# HDMI2.net
KiCad netlist of a schematic drawn in Altium Designer
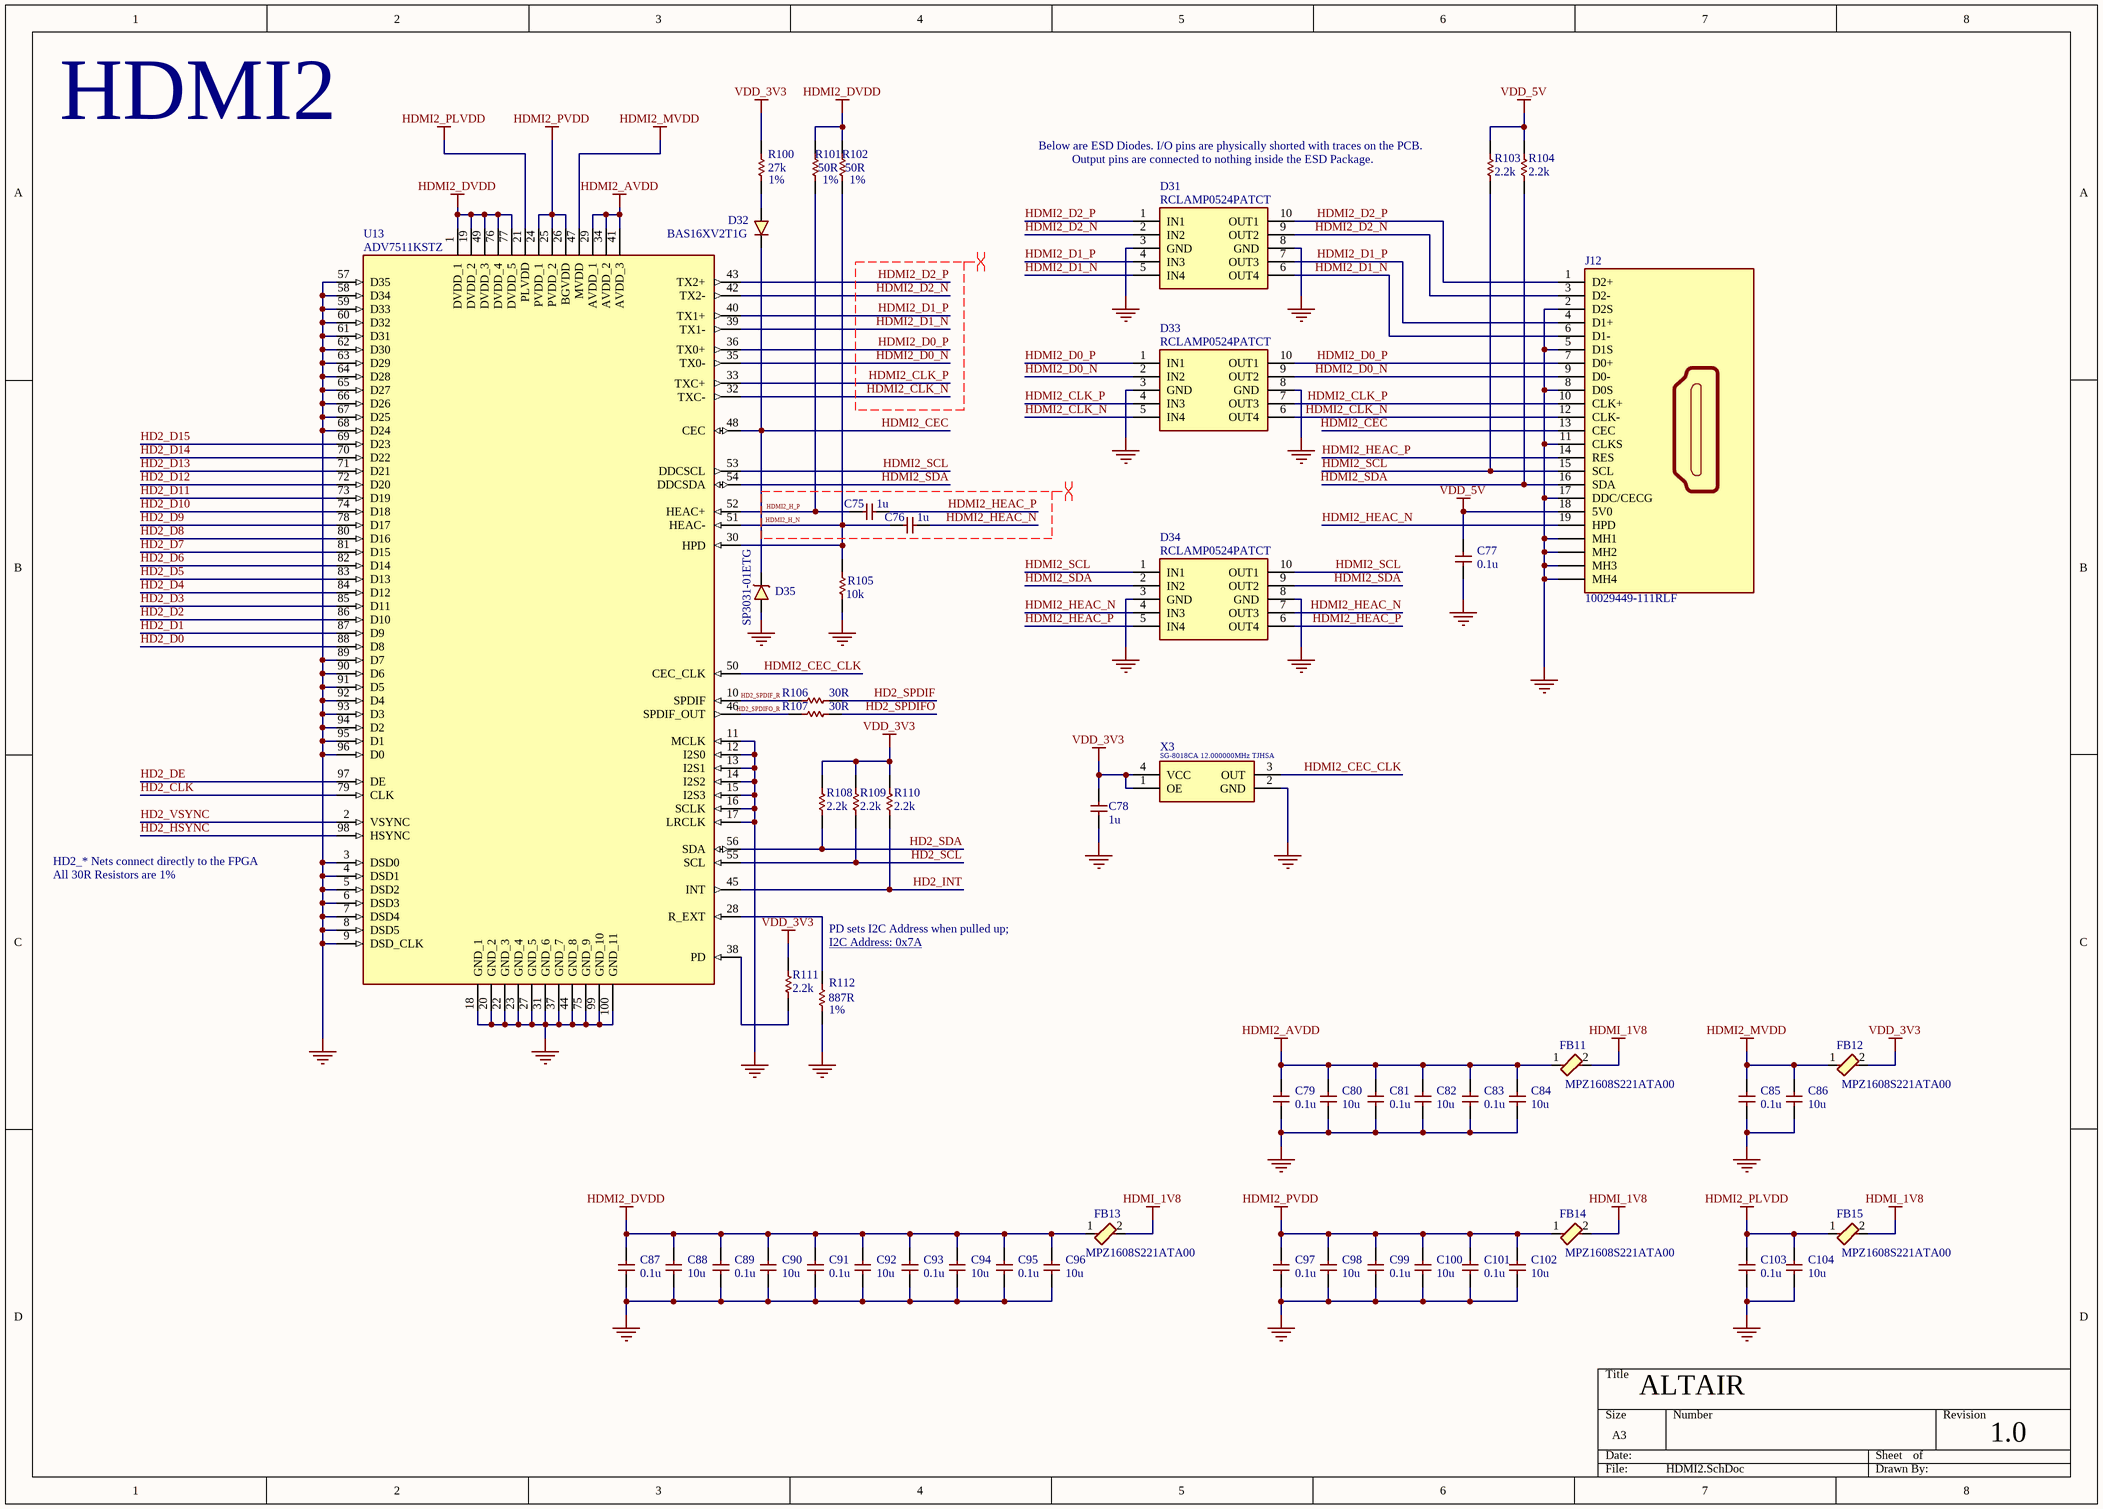
[diagram p0: HDMI2.SchDoc]

(export (version "E")
  (design (tool "Eeschema 10.0.6"))
  (components
    (comp (ref "C75")
      (value "1u")
      (footprint "CAP_0402")
      (description "Capacitor SMD 0402")
      (fields (field (name "JLCPCB PART #") "C14445") (field (name "PART NO") "CL05A105KP5NNNC"))
      (libsource (lib "personalGenericLib") (part "CAP_0402"))
    )
    (comp (ref "C76")
      (value "1u")
      (footprint "CAP_0402")
      (description "Capacitor SMD 0402")
      (fields (field (name "JLCPCB PART #") "C14445") (field (name "PART NO") "CL05A105KP5NNNC"))
      (libsource (lib "personalGenericLib") (part "CAP_0402"))
    )
    (comp (ref "C77")
      (value "0.1u")
      (footprint "CAP_0402")
      (description "Capacitor SMD 0402")
      (fields (field (name "PART NO") "CL05B104KO5NNNC") (field (name "JLCPCB PART #") "C338112"))
      (libsource (lib "personalGenericLib") (part "CAP_0402"))
    )
    (comp (ref "C78")
      (value "1u")
      (footprint "CAP_0402")
      (description "Capacitor SMD 0402")
      (fields (field (name "JLCPCB PART #") "C14445") (field (name "PART NO") "CL05A105KP5NNNC"))
      (libsource (lib "personalGenericLib") (part "CAP_0402"))
    )
    (comp (ref "C79")
      (value "0.1u")
      (footprint "CAP_0402")
      (description "Capacitor SMD 0402")
      (fields (field (name "PART NO") "CL05B104KO5NNNC") (field (name "JLCPCB PART #") "C338112"))
      (libsource (lib "personalGenericLib") (part "CAP_0402"))
    )
    (comp (ref "C80")
      (value "10u")
      (footprint "CAP_0402")
      (description "Capacitor SMD 0402")
      (fields (field (name "JLCPCB PART #") "C315248") (field (name "PART NO") "CL05A106MP5NUNC"))
      (libsource (lib "personalGenericLib") (part "CAP_0402"))
    )
    (comp (ref "C81")
      (value "0.1u")
      (footprint "CAP_0402")
      (description "Capacitor SMD 0402")
      (fields (field (name "PART NO") "CL05B104KO5NNNC") (field (name "JLCPCB PART #") "C338112"))
      (libsource (lib "personalGenericLib") (part "CAP_0402"))
    )
    (comp (ref "C82")
      (value "10u")
      (footprint "CAP_0402")
      (description "Capacitor SMD 0402")
      (fields (field (name "JLCPCB PART #") "C315248") (field (name "PART NO") "CL05A106MP5NUNC"))
      (libsource (lib "personalGenericLib") (part "CAP_0402"))
    )
    (comp (ref "C83")
      (value "0.1u")
      (footprint "CAP_0402")
      (description "Capacitor SMD 0402")
      (fields (field (name "PART NO") "CL05B104KO5NNNC") (field (name "JLCPCB PART #") "C338112"))
      (libsource (lib "personalGenericLib") (part "CAP_0402"))
    )
    (comp (ref "C84")
      (value "10u")
      (footprint "CAP_0402")
      (description "Capacitor SMD 0402")
      (fields (field (name "JLCPCB PART #") "C315248") (field (name "PART NO") "CL05A106MP5NUNC"))
      (libsource (lib "personalGenericLib") (part "CAP_0402"))
    )
    (comp (ref "C85")
      (value "0.1u")
      (footprint "CAP_0402")
      (description "Capacitor SMD 0402")
      (fields (field (name "PART NO") "CL05B104KO5NNNC") (field (name "JLCPCB PART #") "C338112"))
      (libsource (lib "personalGenericLib") (part "CAP_0402"))
    )
    (comp (ref "C86")
      (value "10u")
      (footprint "CAP_0402")
      (description "Capacitor SMD 0402")
      (fields (field (name "JLCPCB PART #") "C315248") (field (name "PART NO") "CL05A106MP5NUNC"))
      (libsource (lib "personalGenericLib") (part "CAP_0402"))
    )
    (comp (ref "C87")
      (value "0.1u")
      (footprint "CAP_0402")
      (description "Capacitor SMD 0402")
      (fields (field (name "PART NO") "CL05B104KO5NNNC") (field (name "JLCPCB PART #") "C338112"))
      (libsource (lib "personalGenericLib") (part "CAP_0402"))
    )
    (comp (ref "C88")
      (value "10u")
      (footprint "CAP_0402")
      (description "Capacitor SMD 0402")
      (fields (field (name "JLCPCB PART #") "C315248") (field (name "PART NO") "CL05A106MP5NUNC"))
      (libsource (lib "personalGenericLib") (part "CAP_0402"))
    )
    (comp (ref "C89")
      (value "0.1u")
      (footprint "CAP_0402")
      (description "Capacitor SMD 0402")
      (fields (field (name "PART NO") "CL05B104KO5NNNC") (field (name "JLCPCB PART #") "C338112"))
      (libsource (lib "personalGenericLib") (part "CAP_0402"))
    )
    (comp (ref "C90")
      (value "10u")
      (footprint "CAP_0402")
      (description "Capacitor SMD 0402")
      (fields (field (name "JLCPCB PART #") "C315248") (field (name "PART NO") "CL05A106MP5NUNC"))
      (libsource (lib "personalGenericLib") (part "CAP_0402"))
    )
    (comp (ref "C91")
      (value "0.1u")
      (footprint "CAP_0402")
      (description "Capacitor SMD 0402")
      (fields (field (name "PART NO") "CL05B104KO5NNNC") (field (name "JLCPCB PART #") "C338112"))
      (libsource (lib "personalGenericLib") (part "CAP_0402"))
    )
    (comp (ref "C92")
      (value "10u")
      (footprint "CAP_0402")
      (description "Capacitor SMD 0402")
      (fields (field (name "JLCPCB PART #") "C315248") (field (name "PART NO") "CL05A106MP5NUNC"))
      (libsource (lib "personalGenericLib") (part "CAP_0402"))
    )
    (comp (ref "C93")
      (value "0.1u")
      (footprint "CAP_0402")
      (description "Capacitor SMD 0402")
      (fields (field (name "PART NO") "CL05B104KO5NNNC") (field (name "JLCPCB PART #") "C338112"))
      (libsource (lib "personalGenericLib") (part "CAP_0402"))
    )
    (comp (ref "C94")
      (value "10u")
      (footprint "CAP_0402")
      (description "Capacitor SMD 0402")
      (fields (field (name "JLCPCB PART #") "C315248") (field (name "PART NO") "CL05A106MP5NUNC"))
      (libsource (lib "personalGenericLib") (part "CAP_0402"))
    )
    (comp (ref "C95")
      (value "0.1u")
      (footprint "CAP_0402")
      (description "Capacitor SMD 0402")
      (fields (field (name "PART NO") "CL05B104KO5NNNC") (field (name "JLCPCB PART #") "C338112"))
      (libsource (lib "personalGenericLib") (part "CAP_0402"))
    )
    (comp (ref "C96")
      (value "10u")
      (footprint "CAP_0402")
      (description "Capacitor SMD 0402")
      (fields (field (name "JLCPCB PART #") "C315248") (field (name "PART NO") "CL05A106MP5NUNC"))
      (libsource (lib "personalGenericLib") (part "CAP_0402"))
    )
    (comp (ref "C97")
      (value "0.1u")
      (footprint "CAP_0402")
      (description "Capacitor SMD 0402")
      (fields (field (name "PART NO") "CL05B104KO5NNNC") (field (name "JLCPCB PART #") "C338112"))
      (libsource (lib "personalGenericLib") (part "CAP_0402"))
    )
    (comp (ref "C98")
      (value "10u")
      (footprint "CAP_0402")
      (description "Capacitor SMD 0402")
      (fields (field (name "JLCPCB PART #") "C315248") (field (name "PART NO") "CL05A106MP5NUNC"))
      (libsource (lib "personalGenericLib") (part "CAP_0402"))
    )
    (comp (ref "C99")
      (value "0.1u")
      (footprint "CAP_0402")
      (description "Capacitor SMD 0402")
      (fields (field (name "PART NO") "CL05B104KO5NNNC") (field (name "JLCPCB PART #") "C338112"))
      (libsource (lib "personalGenericLib") (part "CAP_0402"))
    )
    (comp (ref "C100")
      (value "10u")
      (footprint "CAP_0402")
      (description "Capacitor SMD 0402")
      (fields (field (name "JLCPCB PART #") "C315248") (field (name "PART NO") "CL05A106MP5NUNC"))
      (libsource (lib "personalGenericLib") (part "CAP_0402"))
    )
    (comp (ref "C101")
      (value "0.1u")
      (footprint "CAP_0402")
      (description "Capacitor SMD 0402")
      (fields (field (name "PART NO") "CL05B104KO5NNNC") (field (name "JLCPCB PART #") "C338112"))
      (libsource (lib "personalGenericLib") (part "CAP_0402"))
    )
    (comp (ref "C102")
      (value "10u")
      (footprint "CAP_0402")
      (description "Capacitor SMD 0402")
      (fields (field (name "JLCPCB PART #") "C315248") (field (name "PART NO") "CL05A106MP5NUNC"))
      (libsource (lib "personalGenericLib") (part "CAP_0402"))
    )
    (comp (ref "C103")
      (value "0.1u")
      (footprint "CAP_0402")
      (description "Capacitor SMD 0402")
      (fields (field (name "PART NO") "CL05B104KO5NNNC") (field (name "JLCPCB PART #") "C338112"))
      (libsource (lib "personalGenericLib") (part "CAP_0402"))
    )
    (comp (ref "C104")
      (value "10u")
      (footprint "CAP_0402")
      (description "Capacitor SMD 0402")
      (fields (field (name "JLCPCB PART #") "C315248") (field (name "PART NO") "CL05A106MP5NUNC"))
      (libsource (lib "personalGenericLib") (part "CAP_0402"))
    )
    (comp (ref "D31")
      (value "RCLAMP0524PATCT")
      (footprint "RCLAMP0524PATCT")
      (description "TVS Diode (Uni-directional)")
      (fields (field (name "JLCPCB PART #") "C40960"))
      (libsource (lib "personalGenericLib") (part "RCLAMP0524PATCT"))
    )
    (comp (ref "D32")
      (value "BAS16XV2T1G")
      (footprint "SODFL1608X70N")
      (description "Diode (Switching)")
      (fields (field (name "JLCPCB PART #") "C152479"))
      (libsource (lib "personalGenericLib") (part "BAS16XV2T1G"))
    )
    (comp (ref "D33")
      (value "RCLAMP0524PATCT")
      (footprint "RCLAMP0524PATCT")
      (description "TVS Diode (Uni-directional)")
      (fields (field (name "JLCPCB PART #") "C40960"))
      (libsource (lib "personalGenericLib") (part "RCLAMP0524PATCT"))
    )
    (comp (ref "D34")
      (value "RCLAMP0524PATCT")
      (footprint "RCLAMP0524PATCT")
      (description "TVS Diode (Uni-directional)")
      (fields (field (name "JLCPCB PART #") "C40960"))
      (libsource (lib "personalGenericLib") (part "RCLAMP0524PATCT"))
    )
    (comp (ref "D35")
      (value "SP3031-01ETG")
      (footprint "SP303101ETG")
      (description "TVS Diode (Uni-directional)")
      (fields (field (name "JLCPCB PART #") "C207283"))
      (libsource (lib "personalGenericLib") (part "SP3031-01ETG"))
    )
    (comp (ref "FB11")
      (value "220")
      (footprint "BEADC1608X75N")
      (description "Ferrite Bead")
      (fields (field (name "PART NO") "MPZ1608S221ATA00") (field (name "JLCPCB PART #") "C76815"))
      (libsource (lib "personalGenericLib") (part "MPZ1608S221ATA00"))
    )
    (comp (ref "FB12")
      (value "220")
      (footprint "BEADC1608X75N")
      (description "Ferrite Bead")
      (fields (field (name "PART NO") "MPZ1608S221ATA00") (field (name "JLCPCB PART #") "C76815"))
      (libsource (lib "personalGenericLib") (part "MPZ1608S221ATA00"))
    )
    (comp (ref "FB13")
      (value "220")
      (footprint "BEADC1608X75N")
      (description "Ferrite Bead")
      (fields (field (name "PART NO") "MPZ1608S221ATA00") (field (name "JLCPCB PART #") "C76815"))
      (libsource (lib "personalGenericLib") (part "MPZ1608S221ATA00"))
    )
    (comp (ref "FB14")
      (value "220")
      (footprint "BEADC1608X75N")
      (description "Ferrite Bead")
      (fields (field (name "PART NO") "MPZ1608S221ATA00") (field (name "JLCPCB PART #") "C76815"))
      (libsource (lib "personalGenericLib") (part "MPZ1608S221ATA00"))
    )
    (comp (ref "FB15")
      (value "220")
      (footprint "BEADC1608X75N")
      (description "Ferrite Bead")
      (fields (field (name "PART NO") "MPZ1608S221ATA00") (field (name "JLCPCB PART #") "C76815"))
      (libsource (lib "personalGenericLib") (part "MPZ1608S221ATA00"))
    )
    (comp (ref "J12")
      (value "10029449-111RLF")
      (footprint "10029449111RLF")
      (description "HDMI Connector")
      (fields (field (name "JLCPCB PART #") "C427307"))
      (libsource (lib "personalGenericLib") (part "10029449-111RLF"))
    )
    (comp (ref "R100")
      (value "27k")
      (footprint "RES_0402")
      (description "Resistor SMD 0402")
      (fields
        (field (name "JLCPCB PART #") "C138022")
        (field (name "NOTE/MISC") "1%")
        (field (name "PART NO") "RC0402FR-0727KL")
      )
      (libsource (lib "personalGenericLib") (part "RES_0402"))
    )
    (comp (ref "R101")
      (value "50R")
      (footprint "RES_0402")
      (description "Resistor SMD 0402")
      (fields
        (field (name "JLCPCB PART #") "C853312")
        (field (name "NOTE/MISC") "1%")
        (field (name "PART NO") "RT0402BRE0750RL")
      )
      (libsource (lib "personalGenericLib") (part "RES_0402"))
    )
    (comp (ref "R102")
      (value "50R")
      (footprint "RES_0402")
      (description "Resistor SMD 0402")
      (fields
        (field (name "JLCPCB PART #") "C853312")
        (field (name "NOTE/MISC") "1%")
        (field (name "PART NO") "RT0402BRE0750RL")
      )
      (libsource (lib "personalGenericLib") (part "RES_0402"))
    )
    (comp (ref "R103")
      (value "2.2k")
      (footprint "RES_0402")
      (description "Resistor SMD 0402")
      (fields (field (name "JLCPCB PART #") "C163447") (field (name "PART NO") "RC0402JR-072K2L"))
      (libsource (lib "personalGenericLib") (part "RES_0402"))
    )
    (comp (ref "R104")
      (value "2.2k")
      (footprint "RES_0402")
      (description "Resistor SMD 0402")
      (fields (field (name "JLCPCB PART #") "C163447") (field (name "PART NO") "RC0402JR-072K2L"))
      (libsource (lib "personalGenericLib") (part "RES_0402"))
    )
    (comp (ref "R105")
      (value "10k")
      (footprint "RES_0402")
      (description "Resistor SMD 0402")
      (fields (field (name "JLCPCB PART #") "C60489") (field (name "PART NO") "RC0402JR-0710KL"))
      (libsource (lib "personalGenericLib") (part "RES_0402"))
    )
    (comp (ref "R106")
      (value "30R")
      (footprint "RES_0402")
      (description "Resistor SMD 0402")
      (fields (field (name "JLCPCB PART #") "C138007") (field (name "PART NO") "RC0402FR-0730RL"))
      (libsource (lib "personalGenericLib") (part "RES_0402"))
    )
    (comp (ref "R107")
      (value "30R")
      (footprint "RES_0402")
      (description "Resistor SMD 0402")
      (fields (field (name "JLCPCB PART #") "C138007") (field (name "PART NO") "RC0402FR-0730RL"))
      (libsource (lib "personalGenericLib") (part "RES_0402"))
    )
    (comp (ref "R108")
      (value "2.2k")
      (footprint "RES_0402")
      (description "Resistor SMD 0402")
      (fields (field (name "JLCPCB PART #") "C163447") (field (name "PART NO") "RC0402JR-072K2L"))
      (libsource (lib "personalGenericLib") (part "RES_0402"))
    )
    (comp (ref "R109")
      (value "2.2k")
      (footprint "RES_0402")
      (description "Resistor SMD 0402")
      (fields (field (name "JLCPCB PART #") "C163447") (field (name "PART NO") "RC0402JR-072K2L"))
      (libsource (lib "personalGenericLib") (part "RES_0402"))
    )
    (comp (ref "R110")
      (value "2.2k")
      (footprint "RES_0402")
      (description "Resistor SMD 0402")
      (fields (field (name "JLCPCB PART #") "C163447") (field (name "PART NO") "RC0402JR-072K2L"))
      (libsource (lib "personalGenericLib") (part "RES_0402"))
    )
    (comp (ref "R111")
      (value "2.2k")
      (footprint "RES_0402")
      (description "Resistor SMD 0402")
      (fields (field (name "JLCPCB PART #") "C163447") (field (name "PART NO") "RC0402JR-072K2L"))
      (libsource (lib "personalGenericLib") (part "RES_0402"))
    )
    (comp (ref "R112")
      (value "887R")
      (footprint "RES_0402")
      (description "Resistor SMD 0402")
      (fields
        (field (name "JLCPCB PART #") "C4012675")
        (field (name "NOTE/MISC") "1%")
        (field (name "PART NO") "CRCW0402887RFKED")
      )
      (libsource (lib "personalGenericLib") (part "RES_0402"))
    )
    (comp (ref "U13")
      (value "ADV7511KSTZ")
      (footprint "QFP50P1600X1600X160-100N")
      (description "HDMI RX IC")
      (fields (field (name "JLCPCB PART #") "C179459"))
      (libsource (lib "personalGenericLib") (part "ADV7511KSTZ"))
    )
    (comp (ref "X3")
      (value "SG-8018CA 12.000000MHz TJHSA")
      (footprint "SG8018CA147456MTJHPA3")
      (description "12 MHz Programmable Oscillator")
      (fields (field (name "JLCPCB PART #") "C390417"))
      (libsource (lib "personalGenericLib") (part "SG-8018CA 12.000000MHz TJHSA"))
    )
  )
  (nets
    (net (code "1") (name "/HD2_CLK") (class "Default")
      (node (ref "U13") (pin "79") (pinfunction "CLK_79") (pintype "input"))
    )
    (net (code "2") (name "/HD2_D0") (class "Default")
      (node (ref "U13") (pin "88") (pinfunction "D8_88") (pintype "input"))
    )
    (net (code "3") (name "/HD2_D1") (class "Default")
      (node (ref "U13") (pin "87") (pinfunction "D9_87") (pintype "input"))
    )
    (net (code "4") (name "/HD2_D2") (class "Default")
      (node (ref "U13") (pin "86") (pinfunction "D10_86") (pintype "input"))
    )
    (net (code "5") (name "/HD2_D3") (class "Default")
      (node (ref "U13") (pin "85") (pinfunction "D11_85") (pintype "input"))
    )
    (net (code "6") (name "/HD2_D4") (class "Default")
      (node (ref "U13") (pin "84") (pinfunction "D12_84") (pintype "input"))
    )
    (net (code "7") (name "/HD2_D5") (class "Default")
      (node (ref "U13") (pin "83") (pinfunction "D13_83") (pintype "input"))
    )
    (net (code "8") (name "/HD2_D6") (class "Default")
      (node (ref "U13") (pin "82") (pinfunction "D14_82") (pintype "input"))
    )
    (net (code "9") (name "/HD2_D7") (class "Default")
      (node (ref "U13") (pin "81") (pinfunction "D15_81") (pintype "input"))
    )
    (net (code "10") (name "/HD2_D8") (class "Default")
      (node (ref "U13") (pin "80") (pinfunction "D16_80") (pintype "input"))
    )
    (net (code "11") (name "/HD2_D9") (class "Default")
      (node (ref "U13") (pin "78") (pinfunction "D17_78") (pintype "input"))
    )
    (net (code "12") (name "/HD2_D10") (class "Default")
      (node (ref "U13") (pin "74") (pinfunction "D18_74") (pintype "input"))
    )
    (net (code "13") (name "/HD2_D11") (class "Default")
      (node (ref "U13") (pin "73") (pinfunction "D19_73") (pintype "input"))
    )
    (net (code "14") (name "/HD2_D12") (class "Default")
      (node (ref "U13") (pin "72") (pinfunction "D20_72") (pintype "input"))
    )
    (net (code "15") (name "/HD2_D13") (class "Default")
      (node (ref "U13") (pin "71") (pinfunction "D21_71") (pintype "input"))
    )
    (net (code "16") (name "/HD2_D14") (class "Default")
      (node (ref "U13") (pin "70") (pinfunction "D22_70") (pintype "input"))
    )
    (net (code "17") (name "/HD2_D15") (class "Default")
      (node (ref "U13") (pin "69") (pinfunction "D23_69") (pintype "input"))
    )
    (net (code "18") (name "/HD2_DE") (class "Default")
      (node (ref "U13") (pin "97") (pinfunction "DE_97") (pintype "input"))
    )
    (net (code "19") (name "/HD2_HSYNC") (class "Default")
      (node (ref "U13") (pin "98") (pinfunction "HSYNC_98") (pintype "input"))
    )
    (net (code "20") (name "/HD2_INT") (class "Default")
      (node (ref "R110") (pin "1") (pinfunction "1_1") (pintype "passive"))
      (node (ref "U13") (pin "45") (pinfunction "INT_45") (pintype "output"))
    )
    (net (code "21") (name "/HD2_SCL") (class "Default")
      (node (ref "R109") (pin "1") (pinfunction "1_1") (pintype "passive"))
      (node (ref "U13") (pin "55") (pinfunction "SCL_55") (pintype "input"))
    )
    (net (code "22") (name "/HD2_SDA") (class "Default")
      (node (ref "R108") (pin "1") (pinfunction "1_1") (pintype "passive"))
      (node (ref "U13") (pin "56") (pinfunction "SDA_56") (pintype "bidirectional"))
    )
    (net (code "23") (name "/HD2_SPDIF") (class "Default")
      (node (ref "R106") (pin "2") (pinfunction "2_2") (pintype "passive"))
    )
    (net (code "24") (name "/HD2_SPDIFO") (class "Default")
      (node (ref "R107") (pin "2") (pinfunction "2_2") (pintype "passive"))
    )
    (net (code "25") (name "/HD2_SPDIFO_R") (class "Default")
      (node (ref "R107") (pin "1") (pinfunction "1_1") (pintype "passive"))
      (node (ref "U13") (pin "46") (pinfunction "SPDIF_OUT_46") (pintype "output"))
    )
    (net (code "26") (name "/HD2_SPDIF_R") (class "Default")
      (node (ref "R106") (pin "1") (pinfunction "1_1") (pintype "passive"))
      (node (ref "U13") (pin "10") (pinfunction "SPDIF_10") (pintype "input"))
    )
    (net (code "27") (name "/HD2_VSYNC") (class "Default")
      (node (ref "U13") (pin "2") (pinfunction "VSYNC_2") (pintype "input"))
    )
    (net (code "28") (name "/HDMI2_CEC") (class "Default")
      (node (ref "D32") (pin "1") (pinfunction "K_1") (pintype "passive"))
      (node (ref "D35") (pin "1") (pinfunction "K_1") (pintype "passive"))
      (node (ref "J12") (pin "13") (pinfunction "CEC_13") (pintype "passive"))
      (node (ref "U13") (pin "48") (pinfunction "CEC_48") (pintype "bidirectional"))
    )
    (net (code "29") (name "/HDMI2_CEC_CLK") (class "Default")
      (node (ref "U13") (pin "50") (pinfunction "CEC_CLK_50") (pintype "input"))
      (node (ref "X3") (pin "3") (pinfunction "OUT_3") (pintype "passive"))
    )
    (net (code "30") (name "/HDMI2_CLK_N") (class "Default")
      (node (ref "D33") (pin "5") (pinfunction "IN4_5") (pintype "passive"))
      (node (ref "D33") (pin "6") (pinfunction "OUT4_6") (pintype "passive"))
      (node (ref "J12") (pin "12") (pinfunction "CLK-_12") (pintype "passive"))
      (node (ref "U13") (pin "32") (pinfunction "TXC-_32") (pintype "output"))
    )
    (net (code "31") (name "/HDMI2_CLK_P") (class "Default")
      (node (ref "D33") (pin "4") (pinfunction "IN3_4") (pintype "passive"))
      (node (ref "D33") (pin "7") (pinfunction "OUT3_7") (pintype "passive"))
      (node (ref "J12") (pin "10") (pinfunction "CLK+_10") (pintype "passive"))
      (node (ref "U13") (pin "33") (pinfunction "TXC+_33") (pintype "output"))
    )
    (net (code "32") (name "/HDMI2_D0_N") (class "Default")
      (node (ref "D33") (pin "2") (pinfunction "IN2_2") (pintype "passive"))
      (node (ref "D33") (pin "9") (pinfunction "OUT2_9") (pintype "passive"))
      (node (ref "J12") (pin "9") (pinfunction "D0-_9") (pintype "passive"))
      (node (ref "U13") (pin "35") (pinfunction "TX0-_35") (pintype "output"))
    )
    (net (code "33") (name "/HDMI2_D0_P") (class "Default")
      (node (ref "D33") (pin "1") (pinfunction "IN1_1") (pintype "passive"))
      (node (ref "D33") (pin "10") (pinfunction "OUT1_10") (pintype "passive"))
      (node (ref "J12") (pin "7") (pinfunction "D0+_7") (pintype "passive"))
      (node (ref "U13") (pin "36") (pinfunction "TX0+_36") (pintype "output"))
    )
    (net (code "34") (name "/HDMI2_D1_N") (class "Default")
      (node (ref "D31") (pin "5") (pinfunction "IN4_5") (pintype "passive"))
      (node (ref "D31") (pin "6") (pinfunction "OUT4_6") (pintype "passive"))
      (node (ref "J12") (pin "6") (pinfunction "D1-_6") (pintype "passive"))
      (node (ref "U13") (pin "39") (pinfunction "TX1-_39") (pintype "output"))
    )
    (net (code "35") (name "/HDMI2_D1_P") (class "Default")
      (node (ref "D31") (pin "4") (pinfunction "IN3_4") (pintype "passive"))
      (node (ref "D31") (pin "7") (pinfunction "OUT3_7") (pintype "passive"))
      (node (ref "J12") (pin "4") (pinfunction "D1+_4") (pintype "passive"))
      (node (ref "U13") (pin "40") (pinfunction "TX1+_40") (pintype "output"))
    )
    (net (code "36") (name "/HDMI2_D2_N") (class "Default")
      (node (ref "D31") (pin "2") (pinfunction "IN2_2") (pintype "passive"))
      (node (ref "D31") (pin "9") (pinfunction "OUT2_9") (pintype "passive"))
      (node (ref "J12") (pin "3") (pinfunction "D2-_3") (pintype "passive"))
      (node (ref "U13") (pin "42") (pinfunction "TX2-_42") (pintype "output"))
    )
    (net (code "37") (name "/HDMI2_D2_P") (class "Default")
      (node (ref "D31") (pin "1") (pinfunction "IN1_1") (pintype "passive"))
      (node (ref "D31") (pin "10") (pinfunction "OUT1_10") (pintype "passive"))
      (node (ref "J12") (pin "1") (pinfunction "D2+_1") (pintype "passive"))
      (node (ref "U13") (pin "43") (pinfunction "TX2+_43") (pintype "output"))
    )
    (net (code "38") (name "/HDMI2_HEAC_N") (class "Default")
      (node (ref "C76") (pin "1") (pinfunction "1_1") (pintype "passive"))
      (node (ref "D34") (pin "4") (pinfunction "IN3_4") (pintype "passive"))
      (node (ref "D34") (pin "7") (pinfunction "OUT3_7") (pintype "passive"))
      (node (ref "J12") (pin "19") (pinfunction "HPD_19") (pintype "passive"))
    )
    (net (code "39") (name "/HDMI2_HEAC_P") (class "Default")
      (node (ref "C75") (pin "1") (pinfunction "1_1") (pintype "passive"))
      (node (ref "D34") (pin "5") (pinfunction "IN4_5") (pintype "passive"))
      (node (ref "D34") (pin "6") (pinfunction "OUT4_6") (pintype "passive"))
      (node (ref "J12") (pin "14") (pinfunction "RES_14") (pintype "passive"))
    )
    (net (code "40") (name "/HDMI2_H_N") (class "Default")
      (node (ref "C76") (pin "2") (pinfunction "2_2") (pintype "passive"))
      (node (ref "R102") (pin "2") (pinfunction "2_2") (pintype "passive"))
      (node (ref "R105") (pin "1") (pinfunction "1_1") (pintype "passive"))
      (node (ref "U13") (pin "30") (pinfunction "HPD_30") (pintype "input"))
      (node (ref "U13") (pin "51") (pinfunction "HEAC-_51") (pintype "input"))
    )
    (net (code "41") (name "/HDMI2_H_P") (class "Default")
      (node (ref "C75") (pin "2") (pinfunction "2_2") (pintype "passive"))
      (node (ref "R101") (pin "2") (pinfunction "2_2") (pintype "passive"))
      (node (ref "U13") (pin "52") (pinfunction "HEAC+_52") (pintype "input"))
    )
    (net (code "42") (name "/HDMI2_SCL") (class "Default")
      (node (ref "D34") (pin "1") (pinfunction "IN1_1") (pintype "passive"))
      (node (ref "D34") (pin "10") (pinfunction "OUT1_10") (pintype "passive"))
      (node (ref "J12") (pin "15") (pinfunction "SCL_15") (pintype "passive"))
      (node (ref "R103") (pin "1") (pinfunction "1_1") (pintype "passive"))
      (node (ref "U13") (pin "53") (pinfunction "DDCSCL_53") (pintype "output"))
    )
    (net (code "43") (name "/HDMI2_SDA") (class "Default")
      (node (ref "D34") (pin "2") (pinfunction "IN2_2") (pintype "passive"))
      (node (ref "D34") (pin "9") (pinfunction "OUT2_9") (pintype "passive"))
      (node (ref "J12") (pin "16") (pinfunction "SDA_16") (pintype "passive"))
      (node (ref "R104") (pin "1") (pinfunction "1_1") (pintype "passive"))
      (node (ref "U13") (pin "54") (pinfunction "DDCSDA_54") (pintype "bidirectional"))
    )
    (net (code "44") (name "GND") (class "Default")
      (node (ref "C100") (pin "2") (pinfunction "2_2") (pintype "passive"))
      (node (ref "C101") (pin "1") (pinfunction "1_1") (pintype "passive"))
      (node (ref "C102") (pin "2") (pinfunction "2_2") (pintype "passive"))
      (node (ref "C103") (pin "1") (pinfunction "1_1") (pintype "passive"))
      (node (ref "C104") (pin "2") (pinfunction "2_2") (pintype "passive"))
      (node (ref "C77") (pin "1") (pinfunction "1_1") (pintype "passive"))
      (node (ref "C78") (pin "2") (pinfunction "2_2") (pintype "passive"))
      (node (ref "C79") (pin "1") (pinfunction "1_1") (pintype "passive"))
      (node (ref "C80") (pin "2") (pinfunction "2_2") (pintype "passive"))
      (node (ref "C81") (pin "1") (pinfunction "1_1") (pintype "passive"))
      (node (ref "C82") (pin "2") (pinfunction "2_2") (pintype "passive"))
      (node (ref "C83") (pin "1") (pinfunction "1_1") (pintype "passive"))
      (node (ref "C84") (pin "2") (pinfunction "2_2") (pintype "passive"))
      (node (ref "C85") (pin "1") (pinfunction "1_1") (pintype "passive"))
      (node (ref "C86") (pin "2") (pinfunction "2_2") (pintype "passive"))
      (node (ref "C87") (pin "1") (pinfunction "1_1") (pintype "passive"))
      (node (ref "C88") (pin "2") (pinfunction "2_2") (pintype "passive"))
      (node (ref "C89") (pin "1") (pinfunction "1_1") (pintype "passive"))
      (node (ref "C90") (pin "2") (pinfunction "2_2") (pintype "passive"))
      (node (ref "C91") (pin "1") (pinfunction "1_1") (pintype "passive"))
      (node (ref "C92") (pin "2") (pinfunction "2_2") (pintype "passive"))
      (node (ref "C93") (pin "1") (pinfunction "1_1") (pintype "passive"))
      (node (ref "C94") (pin "2") (pinfunction "2_2") (pintype "passive"))
      (node (ref "C95") (pin "1") (pinfunction "1_1") (pintype "passive"))
      (node (ref "C96") (pin "2") (pinfunction "2_2") (pintype "passive"))
      (node (ref "C97") (pin "1") (pinfunction "1_1") (pintype "passive"))
      (node (ref "C98") (pin "2") (pinfunction "2_2") (pintype "passive"))
      (node (ref "C99") (pin "1") (pinfunction "1_1") (pintype "passive"))
      (node (ref "D31") (pin "3") (pinfunction "GND_3") (pintype "passive"))
      (node (ref "D31") (pin "8") (pinfunction "GND_8") (pintype "passive"))
      (node (ref "D33") (pin "3") (pinfunction "GND_3") (pintype "passive"))
      (node (ref "D33") (pin "8") (pinfunction "GND_8") (pintype "passive"))
      (node (ref "D34") (pin "3") (pinfunction "GND_3") (pintype "passive"))
      (node (ref "D34") (pin "8") (pinfunction "GND_8") (pintype "passive"))
      (node (ref "D35") (pin "2") (pinfunction "A_2") (pintype "passive"))
      (node (ref "J12") (pin "11") (pinfunction "CLKS_11") (pintype "passive"))
      (node (ref "J12") (pin "17") (pinfunction "DDC/CECG_17") (pintype "passive"))
      (node (ref "J12") (pin "2") (pinfunction "D2S_2") (pintype "passive"))
      (node (ref "J12") (pin "5") (pinfunction "D1S_5") (pintype "passive"))
      (node (ref "J12") (pin "8") (pinfunction "D0S_8") (pintype "passive"))
      (node (ref "J12") (pin "MH1") (pinfunction "MH1_MH1") (pintype "passive"))
      (node (ref "J12") (pin "MH2") (pinfunction "MH2_MH2") (pintype "passive"))
      (node (ref "J12") (pin "MH3") (pinfunction "MH3_MH3") (pintype "passive"))
      (node (ref "J12") (pin "MH4") (pinfunction "MH4_MH4") (pintype "passive"))
      (node (ref "R105") (pin "2") (pinfunction "2_2") (pintype "passive"))
      (node (ref "R112") (pin "2") (pinfunction "2_2") (pintype "passive"))
      (node (ref "U13") (pin "100") (pinfunction "GND_11_100") (pintype "power_in"))
      (node (ref "U13") (pin "11") (pinfunction "MCLK_11") (pintype "input"))
      (node (ref "U13") (pin "12") (pinfunction "I2S0_12") (pintype "input"))
      (node (ref "U13") (pin "13") (pinfunction "I2S1_13") (pintype "input"))
      (node (ref "U13") (pin "14") (pinfunction "I2S2_14") (pintype "input"))
      (node (ref "U13") (pin "15") (pinfunction "I2S3_15") (pintype "input"))
      (node (ref "U13") (pin "16") (pinfunction "SCLK_16") (pintype "input"))
      (node (ref "U13") (pin "17") (pinfunction "LRCLK_17") (pintype "input"))
      (node (ref "U13") (pin "18") (pinfunction "GND_1_18") (pintype "power_in"))
      (node (ref "U13") (pin "20") (pinfunction "GND_2_20") (pintype "power_in"))
      (node (ref "U13") (pin "22") (pinfunction "GND_3_22") (pintype "power_in"))
      (node (ref "U13") (pin "23") (pinfunction "GND_4_23") (pintype "power_in"))
      (node (ref "U13") (pin "27") (pinfunction "GND_5_27") (pintype "power_in"))
      (node (ref "U13") (pin "3") (pinfunction "DSD0_3") (pintype "input"))
      (node (ref "U13") (pin "31") (pinfunction "GND_6_31") (pintype "power_in"))
      (node (ref "U13") (pin "37") (pinfunction "GND_7_37") (pintype "power_in"))
      (node (ref "U13") (pin "4") (pinfunction "DSD1_4") (pintype "input"))
      (node (ref "U13") (pin "44") (pinfunction "GND_8_44") (pintype "power_in"))
      (node (ref "U13") (pin "5") (pinfunction "DSD2_5") (pintype "input"))
      (node (ref "U13") (pin "57") (pinfunction "D35_57") (pintype "input"))
      (node (ref "U13") (pin "58") (pinfunction "D34_58") (pintype "input"))
      (node (ref "U13") (pin "59") (pinfunction "D33_59") (pintype "input"))
      (node (ref "U13") (pin "6") (pinfunction "DSD3_6") (pintype "input"))
      (node (ref "U13") (pin "60") (pinfunction "D32_60") (pintype "input"))
      (node (ref "U13") (pin "61") (pinfunction "D31_61") (pintype "input"))
      (node (ref "U13") (pin "62") (pinfunction "D30_62") (pintype "input"))
      (node (ref "U13") (pin "63") (pinfunction "D29_63") (pintype "input"))
      (node (ref "U13") (pin "64") (pinfunction "D28_64") (pintype "input"))
      (node (ref "U13") (pin "65") (pinfunction "D27_65") (pintype "input"))
      (node (ref "U13") (pin "66") (pinfunction "D26_66") (pintype "input"))
      (node (ref "U13") (pin "67") (pinfunction "D25_67") (pintype "input"))
      (node (ref "U13") (pin "68") (pinfunction "D24_68") (pintype "input"))
      (node (ref "U13") (pin "7") (pinfunction "DSD4_7") (pintype "input"))
      (node (ref "U13") (pin "75") (pinfunction "GND_9_75") (pintype "power_in"))
      (node (ref "U13") (pin "8") (pinfunction "DSD5_8") (pintype "input"))
      (node (ref "U13") (pin "89") (pinfunction "D7_89") (pintype "input"))
      (node (ref "U13") (pin "9") (pinfunction "DSD_CLK_9") (pintype "input"))
      (node (ref "U13") (pin "90") (pinfunction "D6_90") (pintype "input"))
      (node (ref "U13") (pin "91") (pinfunction "D5_91") (pintype "input"))
      (node (ref "U13") (pin "92") (pinfunction "D4_92") (pintype "input"))
      (node (ref "U13") (pin "93") (pinfunction "D3_93") (pintype "input"))
      (node (ref "U13") (pin "94") (pinfunction "D2_94") (pintype "input"))
      (node (ref "U13") (pin "95") (pinfunction "D1_95") (pintype "input"))
      (node (ref "U13") (pin "96") (pinfunction "D0_96") (pintype "input"))
      (node (ref "U13") (pin "99") (pinfunction "GND_10_99") (pintype "power_in"))
      (node (ref "X3") (pin "2") (pinfunction "GND_2") (pintype "passive"))
    )
    (net (code "45") (name "HDMI2_AVDD") (class "Default")
      (node (ref "C79") (pin "2") (pinfunction "2_2") (pintype "passive"))
      (node (ref "C80") (pin "1") (pinfunction "1_1") (pintype "passive"))
      (node (ref "C81") (pin "2") (pinfunction "2_2") (pintype "passive"))
      (node (ref "C82") (pin "1") (pinfunction "1_1") (pintype "passive"))
      (node (ref "C83") (pin "2") (pinfunction "2_2") (pintype "passive"))
      (node (ref "C84") (pin "1") (pinfunction "1_1") (pintype "passive"))
      (node (ref "FB11") (pin "1") (pinfunction "1_1") (pintype "passive"))
      (node (ref "U13") (pin "29") (pinfunction "AVDD_1_29") (pintype "power_in"))
      (node (ref "U13") (pin "34") (pinfunction "AVDD_2_34") (pintype "power_in"))
      (node (ref "U13") (pin "41") (pinfunction "AVDD_3_41") (pintype "power_in"))
    )
    (net (code "46") (name "HDMI2_DVDD") (class "Default")
      (node (ref "C87") (pin "2") (pinfunction "2_2") (pintype "passive"))
      (node (ref "C88") (pin "1") (pinfunction "1_1") (pintype "passive"))
      (node (ref "C89") (pin "2") (pinfunction "2_2") (pintype "passive"))
      (node (ref "C90") (pin "1") (pinfunction "1_1") (pintype "passive"))
      (node (ref "C91") (pin "2") (pinfunction "2_2") (pintype "passive"))
      (node (ref "C92") (pin "1") (pinfunction "1_1") (pintype "passive"))
      (node (ref "C93") (pin "2") (pinfunction "2_2") (pintype "passive"))
      (node (ref "C94") (pin "1") (pinfunction "1_1") (pintype "passive"))
      (node (ref "C95") (pin "2") (pinfunction "2_2") (pintype "passive"))
      (node (ref "C96") (pin "1") (pinfunction "1_1") (pintype "passive"))
      (node (ref "FB13") (pin "1") (pinfunction "1_1") (pintype "passive"))
      (node (ref "R101") (pin "1") (pinfunction "1_1") (pintype "passive"))
      (node (ref "R102") (pin "1") (pinfunction "1_1") (pintype "passive"))
      (node (ref "U13") (pin "1") (pinfunction "DVDD_1_1") (pintype "power_in"))
      (node (ref "U13") (pin "19") (pinfunction "DVDD_2_19") (pintype "power_in"))
      (node (ref "U13") (pin "49") (pinfunction "DVDD_3_49") (pintype "power_in"))
      (node (ref "U13") (pin "76") (pinfunction "DVDD_4_76") (pintype "power_in"))
      (node (ref "U13") (pin "77") (pinfunction "DVDD_5_77") (pintype "power_in"))
    )
    (net (code "47") (name "HDMI2_MVDD") (class "Default")
      (node (ref "C85") (pin "2") (pinfunction "2_2") (pintype "passive"))
      (node (ref "C86") (pin "1") (pinfunction "1_1") (pintype "passive"))
      (node (ref "FB12") (pin "1") (pinfunction "1_1") (pintype "passive"))
      (node (ref "U13") (pin "47") (pinfunction "MVDD_47") (pintype "power_in"))
    )
    (net (code "48") (name "HDMI2_PLVDD") (class "Default")
      (node (ref "C103") (pin "2") (pinfunction "2_2") (pintype "passive"))
      (node (ref "C104") (pin "1") (pinfunction "1_1") (pintype "passive"))
      (node (ref "FB15") (pin "1") (pinfunction "1_1") (pintype "passive"))
      (node (ref "U13") (pin "21") (pinfunction "PLVDD_21") (pintype "power_in"))
    )
    (net (code "49") (name "HDMI2_PVDD") (class "Default")
      (node (ref "C100") (pin "1") (pinfunction "1_1") (pintype "passive"))
      (node (ref "C101") (pin "2") (pinfunction "2_2") (pintype "passive"))
      (node (ref "C102") (pin "1") (pinfunction "1_1") (pintype "passive"))
      (node (ref "C97") (pin "2") (pinfunction "2_2") (pintype "passive"))
      (node (ref "C98") (pin "1") (pinfunction "1_1") (pintype "passive"))
      (node (ref "C99") (pin "2") (pinfunction "2_2") (pintype "passive"))
      (node (ref "FB14") (pin "1") (pinfunction "1_1") (pintype "passive"))
      (node (ref "U13") (pin "24") (pinfunction "PVDD_1_24") (pintype "power_in"))
      (node (ref "U13") (pin "25") (pinfunction "PVDD_2_25") (pintype "power_in"))
      (node (ref "U13") (pin "26") (pinfunction "BGVDD_26") (pintype "power_in"))
    )
    (net (code "50") (name "HDMI_1V8") (class "Default")
      (node (ref "FB11") (pin "2") (pinfunction "2_2") (pintype "passive"))
      (node (ref "FB13") (pin "2") (pinfunction "2_2") (pintype "passive"))
      (node (ref "FB14") (pin "2") (pinfunction "2_2") (pintype "passive"))
      (node (ref "FB15") (pin "2") (pinfunction "2_2") (pintype "passive"))
    )
    (net (code "51") (name "Net-(D32-A)") (class "Default")
      (node (ref "D32") (pin "2") (pinfunction "A_2") (pintype "passive"))
      (node (ref "R100") (pin "2") (pinfunction "2_2") (pintype "passive"))
    )
    (net (code "52") (name "Net-(U13-PD)") (class "Default")
      (node (ref "R111") (pin "2") (pinfunction "2_2") (pintype "passive"))
      (node (ref "U13") (pin "38") (pinfunction "PD_38") (pintype "input"))
    )
    (net (code "53") (name "Net-(U13-R_EXT)") (class "Default")
      (node (ref "R112") (pin "1") (pinfunction "1_1") (pintype "passive"))
      (node (ref "U13") (pin "28") (pinfunction "R_EXT_28") (pintype "input"))
    )
    (net (code "54") (name "VDD_3V3") (class "Default")
      (node (ref "C78") (pin "1") (pinfunction "1_1") (pintype "passive"))
      (node (ref "FB12") (pin "2") (pinfunction "2_2") (pintype "passive"))
      (node (ref "R100") (pin "1") (pinfunction "1_1") (pintype "passive"))
      (node (ref "R108") (pin "2") (pinfunction "2_2") (pintype "passive"))
      (node (ref "R109") (pin "2") (pinfunction "2_2") (pintype "passive"))
      (node (ref "R110") (pin "2") (pinfunction "2_2") (pintype "passive"))
      (node (ref "R111") (pin "1") (pinfunction "1_1") (pintype "passive"))
      (node (ref "X3") (pin "1") (pinfunction "OE_1") (pintype "passive"))
      (node (ref "X3") (pin "4") (pinfunction "VCC_4") (pintype "passive"))
    )
    (net (code "55") (name "VDD_5V") (class "Default")
      (node (ref "C77") (pin "2") (pinfunction "2_2") (pintype "passive"))
      (node (ref "J12") (pin "18") (pinfunction "5V0_18") (pintype "passive"))
      (node (ref "R103") (pin "2") (pinfunction "2_2") (pintype "passive"))
      (node (ref "R104") (pin "2") (pinfunction "2_2") (pintype "passive"))
    )
  )
)
